# design.net
KiCad netlist of a schematic drawn in EAGLE
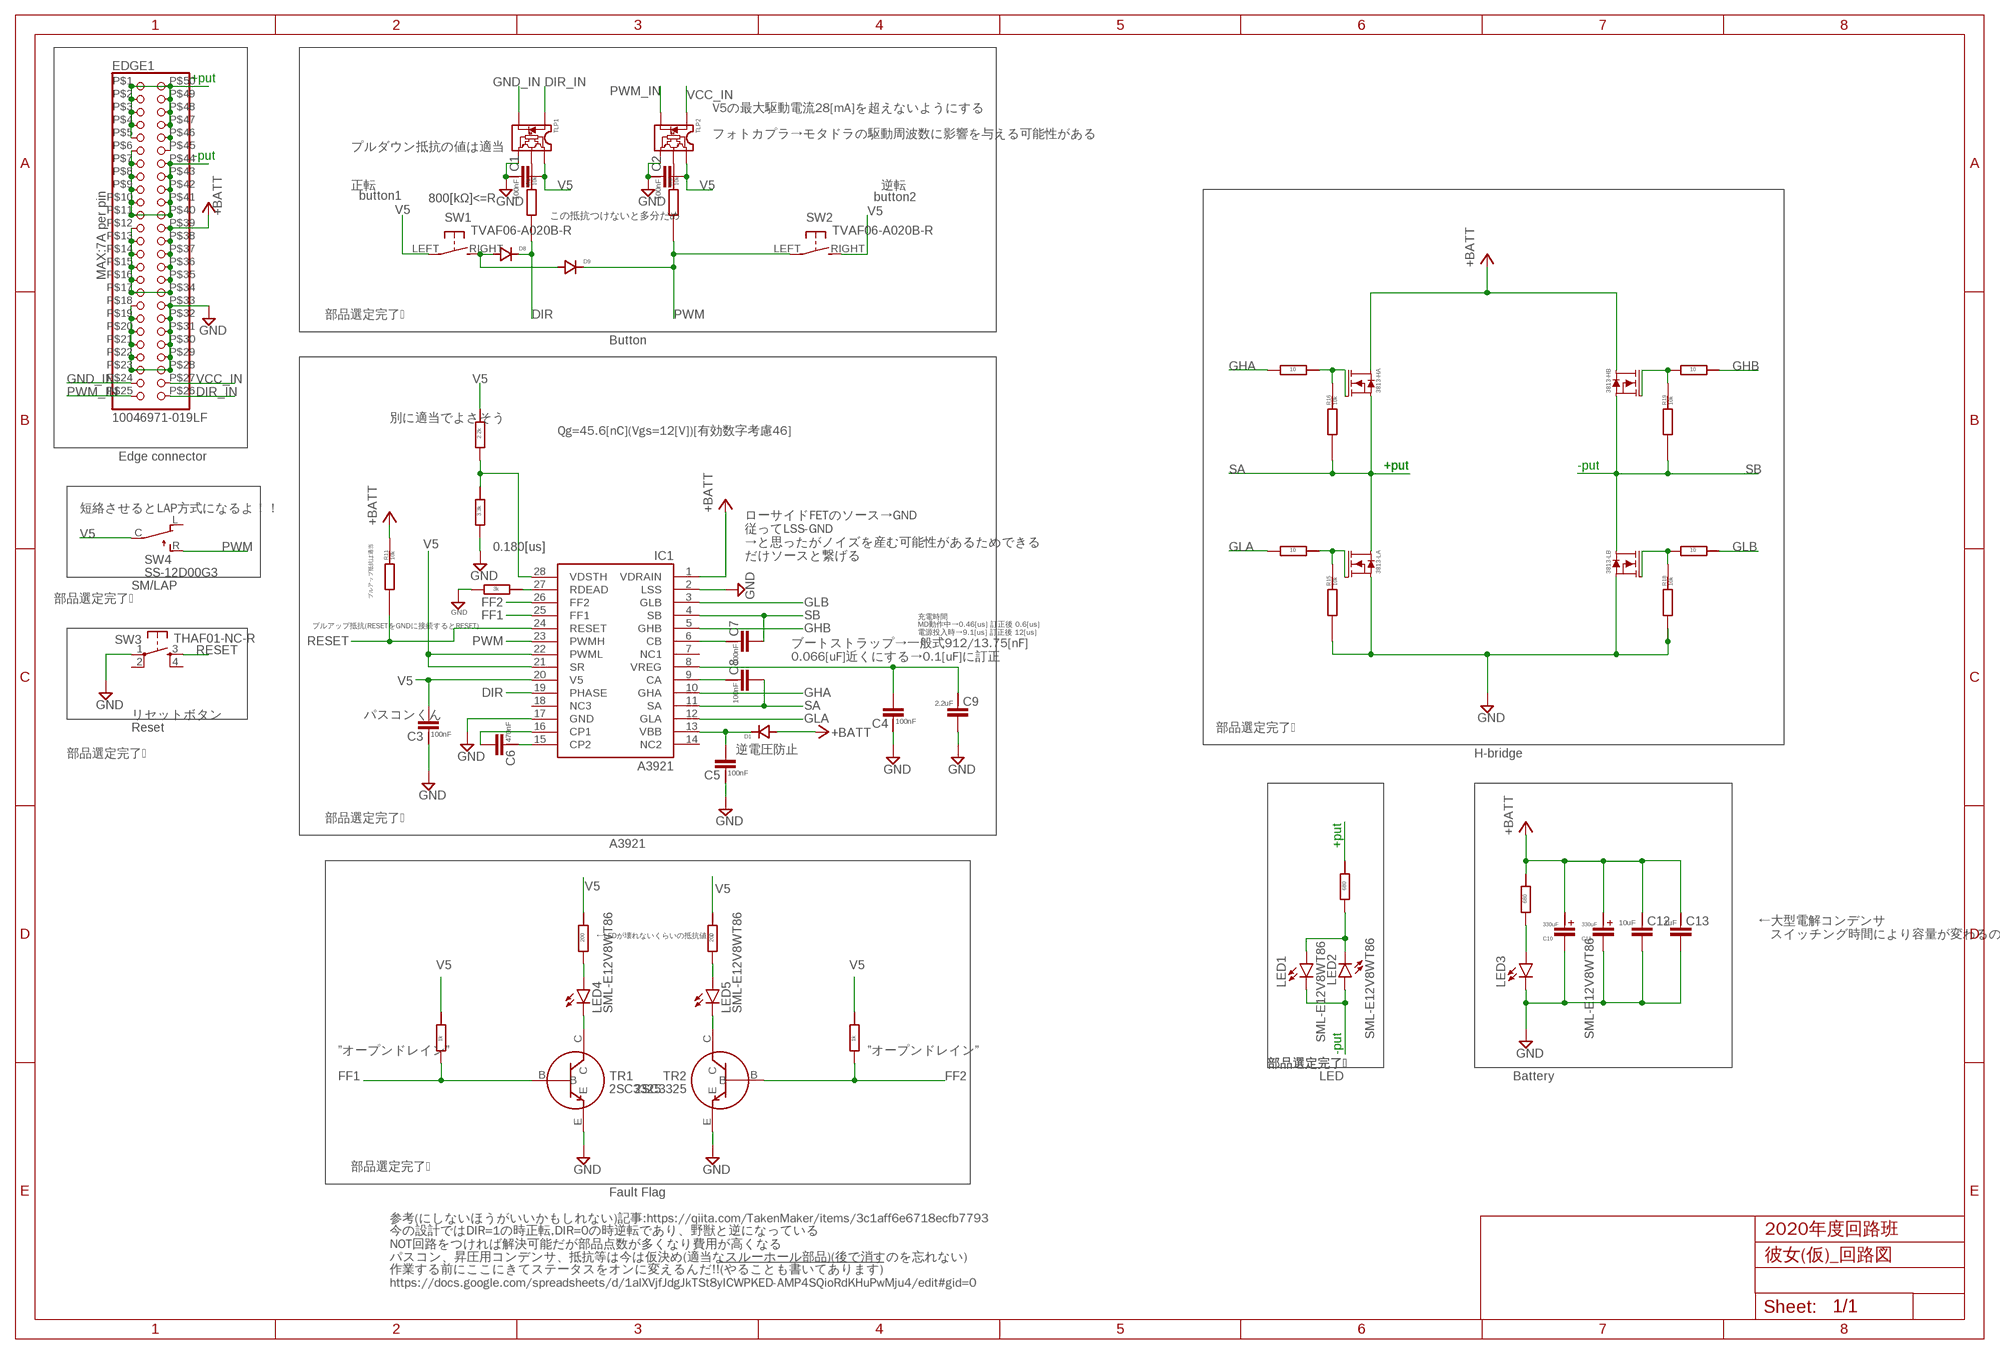
[diagram p0: schematic, sheet 1]

(export (version "E")
  (design (tool "Eeschema 10.0.6"))
  (components
    (comp (ref "3813-HA")
      (value "IRLB3813NOHOLE")
      (footprint "eagle-import:TO-220AB-NOHOLE")
      (libsource (lib "eagle-import") (part "IRLB3813NOHOLE"))
    )
    (comp (ref "3813-HB")
      (value "IRLB3813NOHOLE")
      (footprint "eagle-import:TO-220AB-NOHOLE")
      (libsource (lib "eagle-import") (part "IRLB3813NOHOLE"))
    )
    (comp (ref "3813-LA")
      (value "IRLB3813NOHOLE")
      (footprint "eagle-import:TO-220AB-NOHOLE")
      (libsource (lib "eagle-import") (part "IRLB3813NOHOLE"))
    )
    (comp (ref "3813-LB")
      (value "IRLB3813NOHOLE")
      (footprint "eagle-import:TO-220AB-NOHOLE")
      (libsource (lib "eagle-import") (part "IRLB3813NOHOLE"))
    )
    (comp (ref "C1")
      (value "GCM188L81H104KA57")
      (footprint "eagle-import:GCM188L81H104KA57")
      (libsource (lib "eagle-import") (part "GCM188L81H104KA57"))
    )
    (comp (ref "C2")
      (value "GCM188L81H104KA57")
      (footprint "eagle-import:GCM188L81H104KA57")
      (libsource (lib "eagle-import") (part "GCM188L81H104KA57"))
    )
    (comp (ref "C3")
      (value "GCM188L81H104KA57")
      (footprint "eagle-import:GCM188L81H104KA57")
      (libsource (lib "eagle-import") (part "GCM188L81H104KA57"))
    )
    (comp (ref "C4")
      (value "GCM188L81H104KA57")
      (footprint "eagle-import:GCM188L81H104KA57")
      (libsource (lib "eagle-import") (part "GCM188L81H104KA57"))
    )
    (comp (ref "C5")
      (value "GCM188L81H104KA57")
      (footprint "eagle-import:GCM188L81H104KA57")
      (libsource (lib "eagle-import") (part "GCM188L81H104KA57"))
    )
    (comp (ref "C6")
      (value "GCM21BR71H474KA55")
      (footprint "eagle-import:GCM21BR71H474KA55")
      (libsource (lib "eagle-import") (part "GCM21BR71H474KA55"))
    )
    (comp (ref "C7")
      (value "GCM188L81H104KA57")
      (footprint "eagle-import:GCM188L81H104KA57")
      (libsource (lib "eagle-import") (part "GCM188L81H104KA57"))
    )
    (comp (ref "C8")
      (value "GCM188L81H104KA57")
      (footprint "eagle-import:GCM188L81H104KA57")
      (libsource (lib "eagle-import") (part "GCM188L81H104KA57"))
    )
    (comp (ref "C9")
      (value "GRT31CC81H225KE01L")
      (footprint "eagle-import:GRT31CC81H225KE01L")
      (libsource (lib "eagle-import") (part "GRT31CC81H225KE01L"))
    )
    (comp (ref "C10")
      (value "35PZJ330M10X9")
      (footprint "eagle-import:35PZJ330M10X9")
      (libsource (lib "eagle-import") (part "35PZJ330M10X9"))
    )
    (comp (ref "C11")
      (value "35PZJ330M10X9")
      (footprint "eagle-import:35PZJ330M10X9")
      (libsource (lib "eagle-import") (part "35PZJ330M10X9"))
    )
    (comp (ref "C12")
      (value "GRM32ER7YA106KA12")
      (footprint "eagle-import:GRM32ER7YA106KA12")
      (libsource (lib "eagle-import") (part "GRM32ER7YA106KA12"))
    )
    (comp (ref "C13")
      (value "GRM21BC72A105KE01")
      (footprint "eagle-import:GRM21BC72A105KE01")
      (libsource (lib "eagle-import") (part "GRM21BC72A105KE01"))
    )
    (comp (ref "D1")
      (value "GS1010FL")
      (footprint "eagle-import:GS1010FL")
      (libsource (lib "eagle-import") (part "GS1010FL"))
    )
    (comp (ref "D8")
      (value "GS1010FL")
      (footprint "eagle-import:GS1010FL")
      (libsource (lib "eagle-import") (part "GS1010FL"))
    )
    (comp (ref "D9")
      (value "GS1010FL")
      (footprint "eagle-import:GS1010FL")
      (libsource (lib "eagle-import") (part "GS1010FL"))
    )
    (comp (ref "EDGE1")
      (value "10046971-019LF")
      (footprint "eagle-import:10046971-019LF")
      (libsource (lib "eagle-import") (part "10046971-019LF"))
    )
    (comp (ref "IC1")
      (value "A3921")
      (footprint "eagle-import:A3921")
      (libsource (lib "eagle-import") (part "A3921"))
    )
    (comp (ref "LED1")
      (value "SML-E12V8WT86")
      (footprint "eagle-import:SML-E12V8WT86")
      (libsource (lib "eagle-import") (part "SML-E12V8WT86"))
    )
    (comp (ref "LED2")
      (value "SML-E12V8WT86")
      (footprint "eagle-import:SML-E12V8WT86")
      (libsource (lib "eagle-import") (part "SML-E12V8WT86"))
    )
    (comp (ref "LED3")
      (value "SML-E12V8WT86")
      (footprint "eagle-import:SML-E12V8WT86")
      (libsource (lib "eagle-import") (part "SML-E12V8WT86"))
    )
    (comp (ref "LED4")
      (value "SML-E12V8WT86")
      (footprint "eagle-import:SML-E12V8WT86")
      (libsource (lib "eagle-import") (part "SML-E12V8WT86"))
    )
    (comp (ref "LED5")
      (value "SML-E12V8WT86")
      (footprint "eagle-import:SML-E12V8WT86")
      (libsource (lib "eagle-import") (part "SML-E12V8WT86"))
    )
    (comp (ref "R1")
      (value "RG2012")
      (footprint "eagle-import:RG2012")
      (libsource (lib "eagle-import") (part "RG2012"))
    )
    (comp (ref "R2")
      (value "RG2012N-332-W-T1")
      (footprint "eagle-import:RG2012")
      (libsource (lib "eagle-import") (part "RG2012N-332-W-T1"))
    )
    (comp (ref "R3")
      (value "RG2012P-681-B-T5")
      (footprint "eagle-import:RG2012")
      (libsource (lib "eagle-import") (part "RG2012P-681-B-T5"))
    )
    (comp (ref "R5")
      (value "RG2012-N-102-B-T5")
      (footprint "eagle-import:RG2012")
      (libsource (lib "eagle-import") (part "RG2012-N-102-B-T5"))
    )
    (comp (ref "R6")
      (value "RG2012-N-102-B-T5")
      (footprint "eagle-import:RG2012")
      (libsource (lib "eagle-import") (part "RG2012-N-102-B-T5"))
    )
    (comp (ref "R7")
      (value "RG2012N-201-W-T1")
      (footprint "eagle-import:RG2012")
      (libsource (lib "eagle-import") (part "RG2012N-201-W-T1"))
    )
    (comp (ref "R8")
      (value "RG2012N-201-W-T1")
      (footprint "eagle-import:RG2012")
      (libsource (lib "eagle-import") (part "RG2012N-201-W-T1"))
    )
    (comp (ref "R9")
      (value "RG2012")
      (footprint "eagle-import:RG2012")
      (libsource (lib "eagle-import") (part "RG2012"))
    )
    (comp (ref "R10")
      (value "RG2012Q-100-D-T5")
      (footprint "eagle-import:RG2012")
      (libsource (lib "eagle-import") (part "RG2012Q-100-D-T5"))
    )
    (comp (ref "R11")
      (value "RG2012")
      (footprint "eagle-import:RG2012")
      (libsource (lib "eagle-import") (part "RG2012"))
    )
    (comp (ref "R12")
      (value "RG2012Q-100-D-T5")
      (footprint "eagle-import:RG2012")
      (libsource (lib "eagle-import") (part "RG2012Q-100-D-T5"))
    )
    (comp (ref "R13")
      (value "RG2012P-302-B-T5")
      (footprint "eagle-import:RG2012")
      (libsource (lib "eagle-import") (part "RG2012P-302-B-T5"))
    )
    (comp (ref "R14")
      (value "RG2012N-222-W-T1")
      (footprint "eagle-import:RG2012")
      (libsource (lib "eagle-import") (part "RG2012N-222-W-T1"))
    )
    (comp (ref "R15")
      (value "RG2012")
      (footprint "eagle-import:RG2012")
      (libsource (lib "eagle-import") (part "RG2012"))
    )
    (comp (ref "R16")
      (value "RG2012")
      (footprint "eagle-import:RG2012")
      (libsource (lib "eagle-import") (part "RG2012"))
    )
    (comp (ref "R18")
      (value "RG2012")
      (footprint "eagle-import:RG2012")
      (libsource (lib "eagle-import") (part "RG2012"))
    )
    (comp (ref "R19")
      (value "RG2012")
      (footprint "eagle-import:RG2012")
      (libsource (lib "eagle-import") (part "RG2012"))
    )
    (comp (ref "R20")
      (value "RG2012Q-100-D-T5")
      (footprint "eagle-import:RG2012")
      (libsource (lib "eagle-import") (part "RG2012Q-100-D-T5"))
    )
    (comp (ref "R21")
      (value "RG2012Q-100-D-T5")
      (footprint "eagle-import:RG2012")
      (libsource (lib "eagle-import") (part "RG2012Q-100-D-T5"))
    )
    (comp (ref "R22")
      (value "RG2012P-681-B-T5")
      (footprint "eagle-import:RG2012")
      (libsource (lib "eagle-import") (part "RG2012P-681-B-T5"))
    )
    (comp (ref "SW1")
      (value "TVAF06-A020B-R")
      (footprint "eagle-import:TVAF06-A020B-R")
      (libsource (lib "eagle-import") (part "TVAF06-A020B-R"))
    )
    (comp (ref "SW2")
      (value "TVAF06-A020B-R")
      (footprint "eagle-import:TVAF06-A020B-R")
      (libsource (lib "eagle-import") (part "TVAF06-A020B-R"))
    )
    (comp (ref "SW3")
      (value "THAF01-NC-R")
      (footprint "eagle-import:THAF01-NC-R")
      (libsource (lib "eagle-import") (part "THAF01-NC-R"))
    )
    (comp (ref "SW4")
      (value "SS-12D00G3")
      (footprint "eagle-import:SS-12D00G3")
      (libsource (lib "eagle-import") (part "SS-12D00G3"))
    )
    (comp (ref "TLP1")
      (value "TLP2366")
      (footprint "eagle-import:TLP2366")
      (libsource (lib "eagle-import") (part "TLP2366"))
    )
    (comp (ref "TLP2")
      (value "TLP2366")
      (footprint "eagle-import:TLP2366")
      (libsource (lib "eagle-import") (part "TLP2366"))
    )
    (comp (ref "TR1")
      (value "2SC3325")
      (footprint "eagle-import:2SC3325")
      (libsource (lib "eagle-import") (part "2SC3325"))
    )
    (comp (ref "TR2")
      (value "2SC3325")
      (footprint "eagle-import:2SC3325")
      (libsource (lib "eagle-import") (part "2SC3325"))
    )
  )
  (nets
    (net (code "1") (name "+BATT") (class "Default")
      (node (ref "3813-HA") (pin "DRAIN") (pinfunction "D_DRAIN") (pintype "passive"))
      (node (ref "3813-HB") (pin "DRAIN") (pinfunction "D_DRAIN") (pintype "passive"))
      (node (ref "C10") (pin "A") (pinfunction "ANODE_A") (pintype "bidirectional"))
      (node (ref "C11") (pin "A") (pinfunction "ANODE_A") (pintype "bidirectional"))
      (node (ref "C12") (pin "P$1") (pinfunction "P$1_P$1") (pintype "bidirectional"))
      (node (ref "C13") (pin "P$1") (pinfunction "P$1_P$1") (pintype "bidirectional"))
      (node (ref "D1") (pin "A") (pinfunction "A_A") (pintype "passive"))
      (node (ref "EDGE1") (pin "P$12") (pinfunction "P12_P$12") (pintype "passive"))
      (node (ref "EDGE1") (pin "P$13") (pinfunction "P13_P$13") (pintype "passive"))
      (node (ref "EDGE1") (pin "P$14") (pinfunction "P14_P$14") (pintype "passive"))
      (node (ref "EDGE1") (pin "P$15") (pinfunction "P15_P$15") (pintype "passive"))
      (node (ref "EDGE1") (pin "P$16") (pinfunction "P16_P$16") (pintype "passive"))
      (node (ref "EDGE1") (pin "P$17") (pinfunction "P17_P$17") (pintype "passive"))
      (node (ref "EDGE1") (pin "P$34") (pinfunction "P34_P$34") (pintype "passive"))
      (node (ref "EDGE1") (pin "P$35") (pinfunction "P35_P$35") (pintype "passive"))
      (node (ref "EDGE1") (pin "P$36") (pinfunction "P36_P$36") (pintype "passive"))
      (node (ref "EDGE1") (pin "P$37") (pinfunction "P37_P$37") (pintype "passive"))
      (node (ref "EDGE1") (pin "P$38") (pinfunction "P38_P$38") (pintype "passive"))
      (node (ref "EDGE1") (pin "P$39") (pinfunction "P39_P$39") (pintype "passive"))
      (node (ref "IC1") (pin "1") (pinfunction "VDRAIN_1") (pintype "bidirectional"))
      (node (ref "R11") (pin "RIGHT") (pinfunction "RIGHT_RIGHT") (pintype "bidirectional"))
      (node (ref "R22") (pin "LEFT") (pinfunction "P$1_LEFT") (pintype "bidirectional"))
    )
    (net (code "2") (name "/DIR") (class "Default")
      (node (ref "D8") (pin "C") (pinfunction "C_C") (pintype "passive"))
      (node (ref "IC1") (pin "19") (pinfunction "PHASE_19") (pintype "bidirectional"))
      (node (ref "R1") (pin "LEFT") (pinfunction "LEFT_LEFT") (pintype "bidirectional"))
    )
    (net (code "3") (name "/DIR_IN") (class "Default")
      (node (ref "EDGE1") (pin "P$26") (pinfunction "P26_P$26") (pintype "passive"))
      (node (ref "TLP1") (pin "1") (pinfunction "ANODE_1") (pintype "passive"))
    )
    (net (code "4") (name "/FF1") (class "Default")
      (node (ref "IC1") (pin "25") (pinfunction "FF1_25") (pintype "bidirectional"))
      (node (ref "R5") (pin "RIGHT") (pinfunction "P$2_RIGHT") (pintype "bidirectional"))
      (node (ref "TR1") (pin "B") (pinfunction "B_B") (pintype "bidirectional"))
    )
    (net (code "5") (name "/FF2") (class "Default")
      (node (ref "IC1") (pin "26") (pinfunction "FF2_26") (pintype "bidirectional"))
      (node (ref "R6") (pin "RIGHT") (pinfunction "P$2_RIGHT") (pintype "bidirectional"))
      (node (ref "TR2") (pin "B") (pinfunction "B_B") (pintype "bidirectional"))
    )
    (net (code "6") (name "/GHA") (class "Default")
      (node (ref "IC1") (pin "10") (pinfunction "GHA_10") (pintype "bidirectional"))
      (node (ref "R21") (pin "RIGHT") (pinfunction "P$2_RIGHT") (pintype "bidirectional"))
    )
    (net (code "7") (name "/GHB") (class "Default")
      (node (ref "IC1") (pin "5") (pinfunction "GHB_5") (pintype "bidirectional"))
      (node (ref "R12") (pin "LEFT") (pinfunction "P$1_LEFT") (pintype "bidirectional"))
    )
    (net (code "8") (name "/GLA") (class "Default")
      (node (ref "IC1") (pin "12") (pinfunction "GLA_12") (pintype "bidirectional"))
      (node (ref "R20") (pin "RIGHT") (pinfunction "P$2_RIGHT") (pintype "bidirectional"))
    )
    (net (code "9") (name "/GLB") (class "Default")
      (node (ref "IC1") (pin "3") (pinfunction "GLB_3") (pintype "bidirectional"))
      (node (ref "R10") (pin "LEFT") (pinfunction "P$1_LEFT") (pintype "bidirectional"))
    )
    (net (code "10") (name "/GND_IN") (class "Default")
      (node (ref "EDGE1") (pin "P$24") (pinfunction "P24_P$24") (pintype "passive"))
      (node (ref "TLP1") (pin "3") (pinfunction "CATHODE_3") (pintype "passive"))
    )
    (net (code "11") (name "/PWM") (class "Default")
      (node (ref "D9") (pin "C") (pinfunction "C_C") (pintype "passive"))
      (node (ref "IC1") (pin "23") (pinfunction "PWMH_23") (pintype "bidirectional"))
      (node (ref "R9") (pin "LEFT") (pinfunction "LEFT_LEFT") (pintype "bidirectional"))
      (node (ref "SW2") (pin "LEFT") (pinfunction "P_LEFT") (pintype "passive"))
      (node (ref "SW4") (pin "R") (pinfunction "R_R") (pintype "passive"))
    )
    (net (code "12") (name "/PWM_IN") (class "Default")
      (node (ref "EDGE1") (pin "P$25") (pinfunction "P25_P$25") (pintype "passive"))
      (node (ref "TLP2") (pin "3") (pinfunction "CATHODE_3") (pintype "passive"))
    )
    (net (code "13") (name "/RESET") (class "Default")
      (node (ref "IC1") (pin "24") (pinfunction "RESET_24") (pintype "bidirectional"))
      (node (ref "R11") (pin "LEFT") (pinfunction "LEFT_LEFT") (pintype "bidirectional"))
      (node (ref "SW3") (pin "3") (pinfunction "3_3") (pintype "passive"))
    )
    (net (code "14") (name "/SA") (class "Default")
      (node (ref "3813-HA") (pin "SOURCE") (pinfunction "S_SOURCE") (pintype "passive"))
      (node (ref "3813-LA") (pin "DRAIN") (pinfunction "D_DRAIN") (pintype "passive"))
      (node (ref "C8") (pin "P$2") (pinfunction "P$2_P$2") (pintype "bidirectional"))
      (node (ref "EDGE1") (pin "P$1") (pinfunction "P1_P$1") (pintype "passive"))
      (node (ref "EDGE1") (pin "P$2") (pinfunction "P2_P$2") (pintype "passive"))
      (node (ref "EDGE1") (pin "P$3") (pinfunction "P3_P$3") (pintype "passive"))
      (node (ref "EDGE1") (pin "P$4") (pinfunction "P4_P$4") (pintype "passive"))
      (node (ref "EDGE1") (pin "P$45") (pinfunction "P45_P$45") (pintype "passive"))
      (node (ref "EDGE1") (pin "P$46") (pinfunction "P46_P$46") (pintype "passive"))
      (node (ref "EDGE1") (pin "P$47") (pinfunction "P47_P$47") (pintype "passive"))
      (node (ref "EDGE1") (pin "P$48") (pinfunction "P48_P$48") (pintype "passive"))
      (node (ref "EDGE1") (pin "P$49") (pinfunction "P49_P$49") (pintype "passive"))
      (node (ref "EDGE1") (pin "P$5") (pinfunction "P5_P$5") (pintype "passive"))
      (node (ref "EDGE1") (pin "P$50") (pinfunction "P50_P$50") (pintype "passive"))
      (node (ref "IC1") (pin "11") (pinfunction "SA_11") (pintype "bidirectional"))
      (node (ref "R16") (pin "LEFT") (pinfunction "LEFT_LEFT") (pintype "bidirectional"))
      (node (ref "R3") (pin "LEFT") (pinfunction "P$1_LEFT") (pintype "bidirectional"))
    )
    (net (code "15") (name "/SB") (class "Default")
      (node (ref "3813-HB") (pin "SOURCE") (pinfunction "S_SOURCE") (pintype "passive"))
      (node (ref "3813-LB") (pin "DRAIN") (pinfunction "D_DRAIN") (pintype "passive"))
      (node (ref "C7") (pin "P$2") (pinfunction "P$2_P$2") (pintype "bidirectional"))
      (node (ref "EDGE1") (pin "P$10") (pinfunction "P10_P$10") (pintype "passive"))
      (node (ref "EDGE1") (pin "P$11") (pinfunction "P11_P$11") (pintype "passive"))
      (node (ref "EDGE1") (pin "P$40") (pinfunction "P40_P$40") (pintype "passive"))
      (node (ref "EDGE1") (pin "P$41") (pinfunction "P41_P$41") (pintype "passive"))
      (node (ref "EDGE1") (pin "P$42") (pinfunction "P42_P$42") (pintype "passive"))
      (node (ref "EDGE1") (pin "P$43") (pinfunction "P43_P$43") (pintype "passive"))
      (node (ref "EDGE1") (pin "P$44") (pinfunction "P44_P$44") (pintype "passive"))
      (node (ref "EDGE1") (pin "P$6") (pinfunction "P6_P$6") (pintype "passive"))
      (node (ref "EDGE1") (pin "P$7") (pinfunction "P7_P$7") (pintype "passive"))
      (node (ref "EDGE1") (pin "P$8") (pinfunction "P8_P$8") (pintype "passive"))
      (node (ref "EDGE1") (pin "P$9") (pinfunction "P9_P$9") (pintype "passive"))
      (node (ref "IC1") (pin "4") (pinfunction "SB_4") (pintype "bidirectional"))
      (node (ref "LED1") (pin "K") (pinfunction "C_K") (pintype "passive"))
      (node (ref "LED2") (pin "A") (pinfunction "A_A") (pintype "passive"))
      (node (ref "R19") (pin "LEFT") (pinfunction "LEFT_LEFT") (pintype "bidirectional"))
    )
    (net (code "16") (name "/V5") (class "Default")
      (node (ref "C1") (pin "P$2") (pinfunction "P$2_P$2") (pintype "bidirectional"))
      (node (ref "C2") (pin "P$2") (pinfunction "P$2_P$2") (pintype "bidirectional"))
      (node (ref "C3") (pin "P$2") (pinfunction "P$2_P$2") (pintype "bidirectional"))
      (node (ref "IC1") (pin "20") (pinfunction "V5_20") (pintype "bidirectional"))
      (node (ref "IC1") (pin "21") (pinfunction "SR_21") (pintype "bidirectional"))
      (node (ref "IC1") (pin "22") (pinfunction "PWML_22") (pintype "bidirectional"))
      (node (ref "R14") (pin "LEFT") (pinfunction "P$1_LEFT") (pintype "bidirectional"))
      (node (ref "R5") (pin "LEFT") (pinfunction "P$1_LEFT") (pintype "bidirectional"))
      (node (ref "R6") (pin "LEFT") (pinfunction "P$1_LEFT") (pintype "bidirectional"))
      (node (ref "R7") (pin "LEFT") (pinfunction "P$1_LEFT") (pintype "bidirectional"))
      (node (ref "R8") (pin "LEFT") (pinfunction "P$1_LEFT") (pintype "bidirectional"))
      (node (ref "SW1") (pin "LEFT") (pinfunction "P_LEFT") (pintype "passive"))
      (node (ref "SW2") (pin "RIGHT") (pinfunction "S_RIGHT") (pintype "passive"))
      (node (ref "SW4") (pin "C") (pinfunction "C_C") (pintype "passive"))
      (node (ref "TLP1") (pin "6") (pinfunction "VCC_6") (pintype "passive"))
      (node (ref "TLP2") (pin "6") (pinfunction "VCC_6") (pintype "passive"))
    )
    (net (code "17") (name "/VCC_IN") (class "Default")
      (node (ref "EDGE1") (pin "P$27") (pinfunction "P27_P$27") (pintype "passive"))
      (node (ref "TLP2") (pin "1") (pinfunction "ANODE_1") (pintype "passive"))
    )
    (net (code "18") (name "GND") (class "Default")
      (node (ref "3813-LA") (pin "SOURCE") (pinfunction "S_SOURCE") (pintype "passive"))
      (node (ref "3813-LB") (pin "SOURCE") (pinfunction "S_SOURCE") (pintype "passive"))
      (node (ref "C1") (pin "P$1") (pinfunction "P$1_P$1") (pintype "bidirectional"))
      (node (ref "C10") (pin "C") (pinfunction "CATHODE_C") (pintype "bidirectional"))
      (node (ref "C11") (pin "C") (pinfunction "CATHODE_C") (pintype "bidirectional"))
      (node (ref "C12") (pin "P$2") (pinfunction "P$2_P$2") (pintype "bidirectional"))
      (node (ref "C13") (pin "P$2") (pinfunction "P$2_P$2") (pintype "bidirectional"))
      (node (ref "C2") (pin "P$1") (pinfunction "P$1_P$1") (pintype "bidirectional"))
      (node (ref "C3") (pin "P$1") (pinfunction "P$1_P$1") (pintype "bidirectional"))
      (node (ref "C4") (pin "P$1") (pinfunction "P$1_P$1") (pintype "bidirectional"))
      (node (ref "C5") (pin "P$1") (pinfunction "P$1_P$1") (pintype "bidirectional"))
      (node (ref "C9") (pin "P$2") (pinfunction "P$2_P$2") (pintype "bidirectional"))
      (node (ref "EDGE1") (pin "P$18") (pinfunction "P18_P$18") (pintype "passive"))
      (node (ref "EDGE1") (pin "P$19") (pinfunction "P19_P$19") (pintype "passive"))
      (node (ref "EDGE1") (pin "P$20") (pinfunction "P20_P$20") (pintype "passive"))
      (node (ref "EDGE1") (pin "P$21") (pinfunction "P21_P$21") (pintype "passive"))
      (node (ref "EDGE1") (pin "P$22") (pinfunction "P22_P$22") (pintype "passive"))
      (node (ref "EDGE1") (pin "P$23") (pinfunction "P23_P$23") (pintype "passive"))
      (node (ref "EDGE1") (pin "P$28") (pinfunction "P28_P$28") (pintype "passive"))
      (node (ref "EDGE1") (pin "P$29") (pinfunction "P29_P$29") (pintype "passive"))
      (node (ref "EDGE1") (pin "P$30") (pinfunction "P30_P$30") (pintype "passive"))
      (node (ref "EDGE1") (pin "P$31") (pinfunction "P31_P$31") (pintype "passive"))
      (node (ref "EDGE1") (pin "P$32") (pinfunction "P32_P$32") (pintype "passive"))
      (node (ref "EDGE1") (pin "P$33") (pinfunction "P33_P$33") (pintype "passive"))
      (node (ref "IC1") (pin "17") (pinfunction "GND_17") (pintype "bidirectional"))
      (node (ref "IC1") (pin "2") (pinfunction "LSS_2") (pintype "bidirectional"))
      (node (ref "LED3") (pin "K") (pinfunction "C_K") (pintype "passive"))
      (node (ref "R13") (pin "RIGHT") (pinfunction "P$2_RIGHT") (pintype "bidirectional"))
      (node (ref "R15") (pin "LEFT") (pinfunction "LEFT_LEFT") (pintype "bidirectional"))
      (node (ref "R18") (pin "LEFT") (pinfunction "LEFT_LEFT") (pintype "bidirectional"))
      (node (ref "R2") (pin "RIGHT") (pinfunction "P$2_RIGHT") (pintype "bidirectional"))
      (node (ref "SW3") (pin "1") (pinfunction "1_1") (pintype "passive"))
      (node (ref "TLP1") (pin "4") (pinfunction "GND_4") (pintype "passive"))
      (node (ref "TLP2") (pin "4") (pinfunction "GND_4") (pintype "passive"))
      (node (ref "TR1") (pin "E") (pinfunction "E_E") (pintype "bidirectional"))
      (node (ref "TR2") (pin "E") (pinfunction "E_E") (pintype "bidirectional"))
    )
    (net (code "19") (name "Net-(3813-HA-G)") (class "Default")
      (node (ref "3813-HA") (pin "GATE") (pinfunction "G_GATE") (pintype "passive"))
      (node (ref "R16") (pin "RIGHT") (pinfunction "RIGHT_RIGHT") (pintype "bidirectional"))
      (node (ref "R21") (pin "LEFT") (pinfunction "P$1_LEFT") (pintype "bidirectional"))
    )
    (net (code "20") (name "Net-(3813-HB-G)") (class "Default")
      (node (ref "3813-HB") (pin "GATE") (pinfunction "G_GATE") (pintype "passive"))
      (node (ref "R12") (pin "RIGHT") (pinfunction "P$2_RIGHT") (pintype "bidirectional"))
      (node (ref "R19") (pin "RIGHT") (pinfunction "RIGHT_RIGHT") (pintype "bidirectional"))
    )
    (net (code "21") (name "Net-(3813-LA-G)") (class "Default")
      (node (ref "3813-LA") (pin "GATE") (pinfunction "G_GATE") (pintype "passive"))
      (node (ref "R15") (pin "RIGHT") (pinfunction "RIGHT_RIGHT") (pintype "bidirectional"))
      (node (ref "R20") (pin "LEFT") (pinfunction "P$1_LEFT") (pintype "bidirectional"))
    )
    (net (code "22") (name "Net-(3813-LB-G)") (class "Default")
      (node (ref "3813-LB") (pin "GATE") (pinfunction "G_GATE") (pintype "passive"))
      (node (ref "R10") (pin "RIGHT") (pinfunction "P$2_RIGHT") (pintype "bidirectional"))
      (node (ref "R18") (pin "RIGHT") (pinfunction "RIGHT_RIGHT") (pintype "bidirectional"))
    )
    (net (code "23") (name "Net-(IC1-CA)") (class "Default")
      (node (ref "C8") (pin "P$1") (pinfunction "P$1_P$1") (pintype "bidirectional"))
      (node (ref "IC1") (pin "9") (pinfunction "CA_9") (pintype "bidirectional"))
    )
    (net (code "24") (name "Net-(IC1-CB)") (class "Default")
      (node (ref "C7") (pin "P$1") (pinfunction "P$1_P$1") (pintype "bidirectional"))
      (node (ref "IC1") (pin "6") (pinfunction "CB_6") (pintype "bidirectional"))
    )
    (net (code "25") (name "Net-(IC1-CP1)") (class "Default")
      (node (ref "C6") (pin "P$2") (pinfunction "P$2_P$2") (pintype "bidirectional"))
      (node (ref "IC1") (pin "16") (pinfunction "CP1_16") (pintype "bidirectional"))
    )
    (net (code "26") (name "Net-(IC1-CP2)") (class "Default")
      (node (ref "C6") (pin "P$1") (pinfunction "P$1_P$1") (pintype "bidirectional"))
      (node (ref "IC1") (pin "15") (pinfunction "CP2_15") (pintype "bidirectional"))
    )
    (net (code "27") (name "Net-(IC1-RDEAD)") (class "Default")
      (node (ref "IC1") (pin "27") (pinfunction "RDEAD_27") (pintype "bidirectional"))
      (node (ref "R13") (pin "LEFT") (pinfunction "P$1_LEFT") (pintype "bidirectional"))
    )
    (net (code "28") (name "Net-(IC1-VBB)") (class "Default")
      (node (ref "C5") (pin "P$2") (pinfunction "P$2_P$2") (pintype "bidirectional"))
      (node (ref "D1") (pin "C") (pinfunction "C_C") (pintype "passive"))
      (node (ref "IC1") (pin "13") (pinfunction "VBB_13") (pintype "bidirectional"))
    )
    (net (code "29") (name "Net-(IC1-VDSTH)") (class "Default")
      (node (ref "IC1") (pin "28") (pinfunction "VDSTH_28") (pintype "bidirectional"))
      (node (ref "R14") (pin "RIGHT") (pinfunction "P$2_RIGHT") (pintype "bidirectional"))
      (node (ref "R2") (pin "LEFT") (pinfunction "P$1_LEFT") (pintype "bidirectional"))
    )
    (net (code "30") (name "Net-(IC1-VREG)") (class "Default")
      (node (ref "C4") (pin "P$2") (pinfunction "P$2_P$2") (pintype "bidirectional"))
      (node (ref "C9") (pin "P$1") (pinfunction "P$1_P$1") (pintype "bidirectional"))
      (node (ref "IC1") (pin "8") (pinfunction "VREG_8") (pintype "bidirectional"))
    )
    (net (code "31") (name "Net-(LED2-C)") (class "Default")
      (node (ref "LED1") (pin "A") (pinfunction "A_A") (pintype "passive"))
      (node (ref "LED2") (pin "K") (pinfunction "C_K") (pintype "passive"))
      (node (ref "R3") (pin "RIGHT") (pinfunction "P$2_RIGHT") (pintype "bidirectional"))
    )
    (net (code "32") (name "Net-(LED4-C)") (class "Default")
      (node (ref "LED4") (pin "K") (pinfunction "C_K") (pintype "passive"))
      (node (ref "TR1") (pin "C") (pinfunction "C_C") (pintype "bidirectional"))
    )
    (net (code "33") (name "Net-(LED5-C)") (class "Default")
      (node (ref "LED5") (pin "K") (pinfunction "C_K") (pintype "passive"))
      (node (ref "TR2") (pin "C") (pinfunction "C_C") (pintype "bidirectional"))
    )
    (net (code "34") (name "Net-(R7-P$2)") (class "Default")
      (node (ref "LED4") (pin "A") (pinfunction "A_A") (pintype "passive"))
      (node (ref "R7") (pin "RIGHT") (pinfunction "P$2_RIGHT") (pintype "bidirectional"))
    )
    (net (code "35") (name "Net-(R8-P$2)") (class "Default")
      (node (ref "LED5") (pin "A") (pinfunction "A_A") (pintype "passive"))
      (node (ref "R8") (pin "RIGHT") (pinfunction "P$2_RIGHT") (pintype "bidirectional"))
    )
    (net (code "36") (name "Net-(R22-P$2)") (class "Default")
      (node (ref "LED3") (pin "A") (pinfunction "A_A") (pintype "passive"))
      (node (ref "R22") (pin "RIGHT") (pinfunction "P$2_RIGHT") (pintype "bidirectional"))
    )
    (net (code "37") (name "Net-(SW1-S)") (class "Default")
      (node (ref "D8") (pin "A") (pinfunction "A_A") (pintype "passive"))
      (node (ref "D9") (pin "A") (pinfunction "A_A") (pintype "passive"))
      (node (ref "SW1") (pin "RIGHT") (pinfunction "S_RIGHT") (pintype "passive"))
    )
    (net (code "38") (name "Net-(TLP1-VOUT)") (class "Default")
      (node (ref "R1") (pin "RIGHT") (pinfunction "RIGHT_RIGHT") (pintype "bidirectional"))
      (node (ref "TLP1") (pin "5") (pinfunction "VOUT_5") (pintype "passive"))
    )
    (net (code "39") (name "Net-(TLP2-VOUT)") (class "Default")
      (node (ref "R9") (pin "RIGHT") (pinfunction "RIGHT_RIGHT") (pintype "bidirectional"))
      (node (ref "TLP2") (pin "5") (pinfunction "VOUT_5") (pintype "passive"))
    )
    (net (code "40") (name "unconnected-(IC1-NC1-Pad7)") (class "Default")
      (node (ref "IC1") (pin "7") (pinfunction "NC1_7") (pintype "bidirectional"))
    )
    (net (code "41") (name "unconnected-(IC1-NC2-Pad14)") (class "Default")
      (node (ref "IC1") (pin "14") (pinfunction "NC2_14") (pintype "bidirectional"))
    )
    (net (code "42") (name "unconnected-(IC1-NC3-Pad18)") (class "Default")
      (node (ref "IC1") (pin "18") (pinfunction "NC3_18") (pintype "bidirectional"))
    )
    (net (code "43") (name "unconnected-(SW3-Pad2)") (class "Default")
      (node (ref "SW3") (pin "2") (pinfunction "2_2") (pintype "passive"))
    )
    (net (code "44") (name "unconnected-(SW3-Pad4)") (class "Default")
      (node (ref "SW3") (pin "4") (pinfunction "4_4") (pintype "passive"))
    )
    (net (code "45") (name "unconnected-(SW4-PadL)") (class "Default")
      (node (ref "SW4") (pin "L") (pinfunction "L_L") (pintype "passive"))
    )
  )
)
